# board.net
KiCad netlist of a schematic drawn in EAGLE
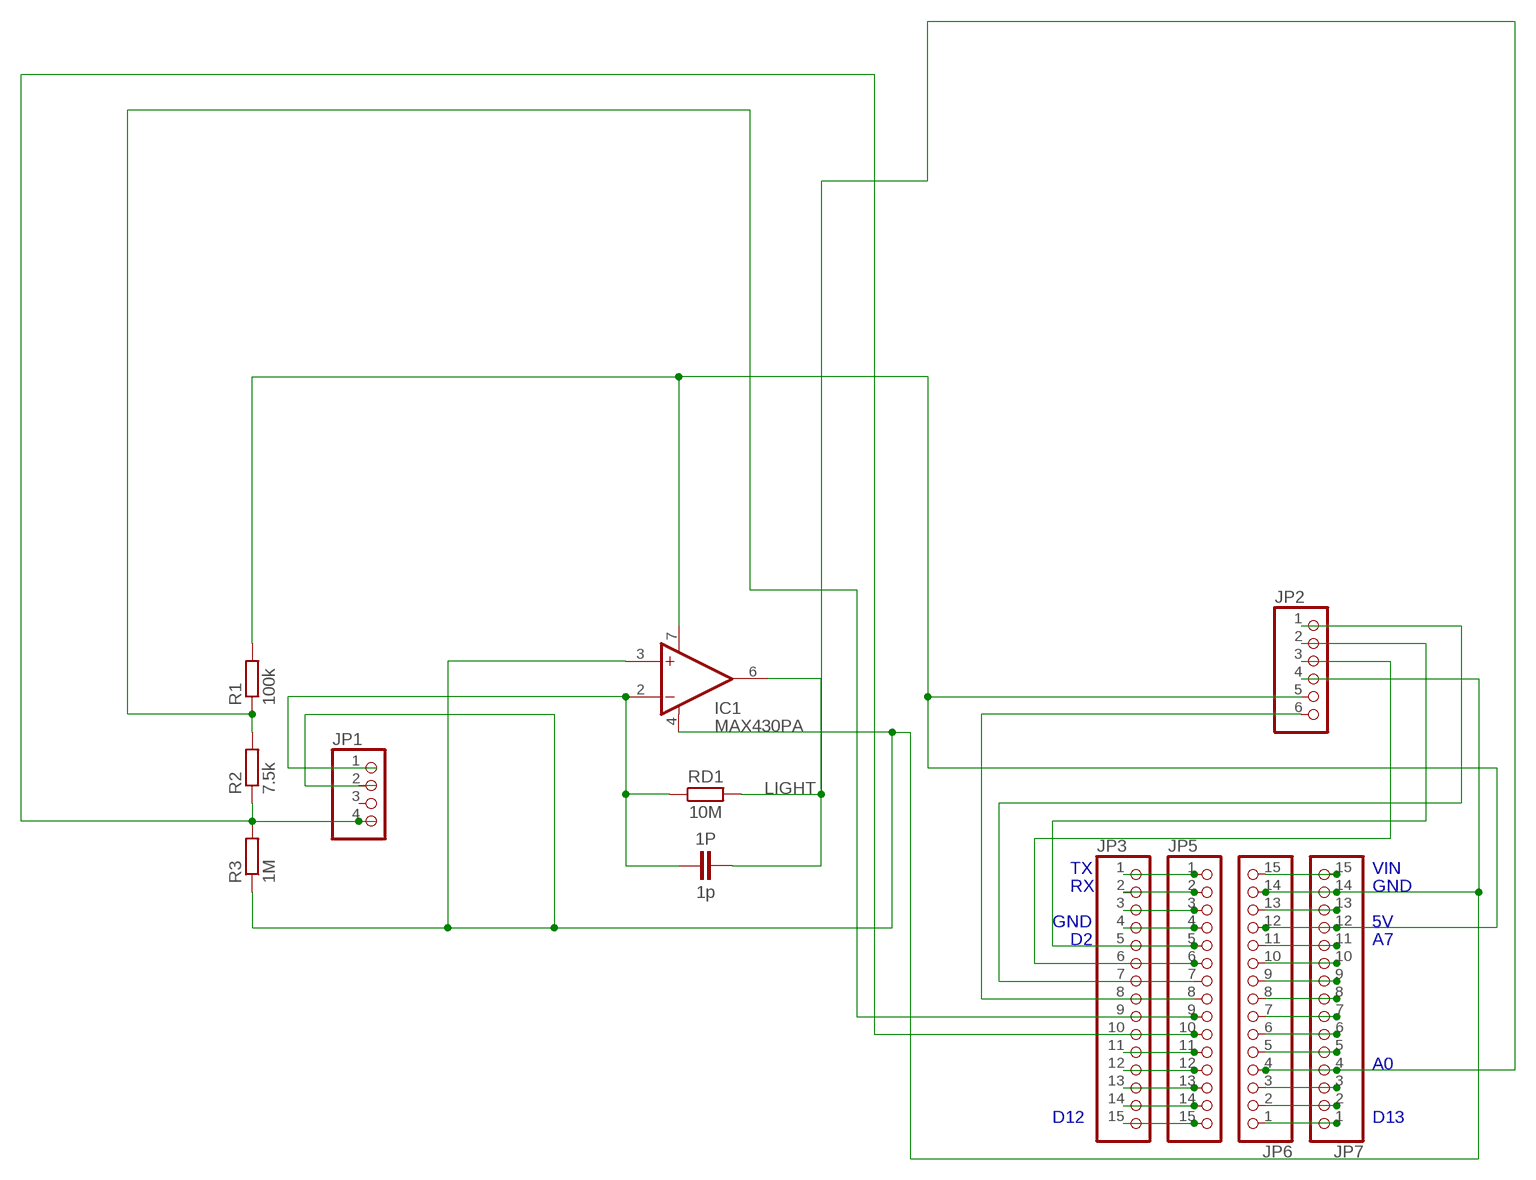
[diagram p0: schematic, sheet 1]

(export (version "E")
  (design (tool "Eeschema 10.0.6"))
  (components
    (comp (ref "1P")
      (value "1p")
      (footprint "eagle-import:1206")
      (libsource (lib "eagle-import") (part "CAPACITOR1206"))
    )
    (comp (ref "IC1")
      (value "MAX430PA")
      (footprint "eagle-import:DIL08")
      (libsource (lib "eagle-import") (part "MAX430PA"))
    )
    (comp (ref "JP1")
      (value "PINHD-1X4")
      (footprint "eagle-import:1X04")
      (libsource (lib "eagle-import") (part "PINHD-1X4"))
    )
    (comp (ref "JP2")
      (value "PINHD-1X6")
      (footprint "eagle-import:1X06")
      (libsource (lib "eagle-import") (part "PINHD-1X6"))
    )
    (comp (ref "JP3")
      (value "PINHD-1X15")
      (footprint "eagle-import:1X15")
      (libsource (lib "eagle-import") (part "PINHD-1X15"))
    )
    (comp (ref "JP5")
      (value "PINHD-1X15")
      (footprint "eagle-import:1X15")
      (libsource (lib "eagle-import") (part "PINHD-1X15"))
    )
    (comp (ref "JP6")
      (value "PINHD-1X15")
      (footprint "eagle-import:1X15")
      (libsource (lib "eagle-import") (part "PINHD-1X15"))
    )
    (comp (ref "JP7")
      (value "PINHD-1X15")
      (footprint "eagle-import:1X15")
      (libsource (lib "eagle-import") (part "PINHD-1X15"))
    )
    (comp (ref "R1")
      (value "100k")
      (footprint "eagle-import:R1206")
      (libsource (lib "eagle-import") (part "R-EU_R1206"))
    )
    (comp (ref "R2")
      (value "7.5k")
      (footprint "eagle-import:R1206")
      (libsource (lib "eagle-import") (part "R-EU_R1206"))
    )
    (comp (ref "R3")
      (value "1M")
      (footprint "eagle-import:R1206")
      (libsource (lib "eagle-import") (part "R-EU_R1206"))
    )
    (comp (ref "RD1")
      (value "10M")
      (footprint "eagle-import:1206")
      (libsource (lib "eagle-import") (part "RESISTOR1206"))
    )
  )
  (nets
    (net (code "1") (name "/LIGHT") (class "Default")
      (node (ref "1P") (pin "2") (pinfunction "2_2") (pintype "passive"))
      (node (ref "IC1") (pin "6") (pinfunction "OUT_6") (pintype "output"))
      (node (ref "JP6") (pin "4") (pinfunction "4_4") (pintype "passive"))
      (node (ref "JP7") (pin "4") (pinfunction "4_4") (pintype "passive"))
      (node (ref "RD1") (pin "2") (pinfunction "2_2") (pintype "passive"))
    )
    (net (code "2") (name "Net-(IC1-+IN)") (class "Default")
      (node (ref "IC1") (pin "3") (pinfunction "+IN_3") (pintype "input"))
      (node (ref "IC1") (pin "4") (pinfunction "V-_4") (pintype "power_in"))
      (node (ref "JP1") (pin "2") (pinfunction "2_2") (pintype "passive"))
      (node (ref "JP2") (pin "4") (pinfunction "4_4") (pintype "passive"))
      (node (ref "JP6") (pin "14") (pinfunction "14_14") (pintype "passive"))
      (node (ref "JP7") (pin "14") (pinfunction "14_14") (pintype "passive"))
      (node (ref "R3") (pin "1") (pinfunction "1_1") (pintype "passive"))
    )
    (net (code "3") (name "Net-(IC1--IN)") (class "Default")
      (node (ref "1P") (pin "1") (pinfunction "1_1") (pintype "passive"))
      (node (ref "IC1") (pin "2") (pinfunction "-IN_2") (pintype "input"))
      (node (ref "JP1") (pin "1") (pinfunction "1_1") (pintype "passive"))
      (node (ref "RD1") (pin "1") (pinfunction "1_1") (pintype "passive"))
    )
    (net (code "4") (name "Net-(IC1-V+)") (class "Default")
      (node (ref "IC1") (pin "7") (pinfunction "V+_7") (pintype "power_in"))
      (node (ref "JP2") (pin "5") (pinfunction "5_5") (pintype "passive"))
      (node (ref "JP6") (pin "12") (pinfunction "12_12") (pintype "passive"))
      (node (ref "JP7") (pin "12") (pinfunction "12_12") (pintype "passive"))
      (node (ref "R1") (pin "2") (pinfunction "2_2") (pintype "passive"))
    )
    (net (code "5") (name "Net-(JP1-Pad4)") (class "Default")
      (node (ref "JP1") (pin "4") (pinfunction "4_4") (pintype "passive"))
      (node (ref "JP3") (pin "10") (pinfunction "10_10") (pintype "passive"))
      (node (ref "JP5") (pin "10") (pinfunction "10_10") (pintype "passive"))
      (node (ref "R2") (pin "1") (pinfunction "1_1") (pintype "passive"))
      (node (ref "R3") (pin "2") (pinfunction "2_2") (pintype "passive"))
    )
    (net (code "6") (name "Net-(JP2-Pad1)") (class "Default")
      (node (ref "JP2") (pin "1") (pinfunction "1_1") (pintype "passive"))
      (node (ref "JP3") (pin "7") (pinfunction "7_7") (pintype "passive"))
      (node (ref "JP5") (pin "7") (pinfunction "7_7") (pintype "passive"))
    )
    (net (code "7") (name "Net-(JP2-Pad2)") (class "Default")
      (node (ref "JP2") (pin "2") (pinfunction "2_2") (pintype "passive"))
      (node (ref "JP3") (pin "5") (pinfunction "5_5") (pintype "passive"))
      (node (ref "JP5") (pin "5") (pinfunction "5_5") (pintype "passive"))
    )
    (net (code "8") (name "Net-(JP2-Pad3)") (class "Default")
      (node (ref "JP2") (pin "3") (pinfunction "3_3") (pintype "passive"))
      (node (ref "JP3") (pin "6") (pinfunction "6_6") (pintype "passive"))
      (node (ref "JP5") (pin "6") (pinfunction "6_6") (pintype "passive"))
    )
    (net (code "9") (name "Net-(JP2-Pad6)") (class "Default")
      (node (ref "JP2") (pin "6") (pinfunction "6_6") (pintype "passive"))
      (node (ref "JP3") (pin "8") (pinfunction "8_8") (pintype "passive"))
      (node (ref "JP5") (pin "8") (pinfunction "8_8") (pintype "passive"))
    )
    (net (code "10") (name "Net-(JP3-Pad1)") (class "Default")
      (node (ref "JP3") (pin "1") (pinfunction "1_1") (pintype "passive"))
      (node (ref "JP5") (pin "1") (pinfunction "1_1") (pintype "passive"))
    )
    (net (code "11") (name "Net-(JP3-Pad2)") (class "Default")
      (node (ref "JP3") (pin "2") (pinfunction "2_2") (pintype "passive"))
      (node (ref "JP5") (pin "2") (pinfunction "2_2") (pintype "passive"))
    )
    (net (code "12") (name "Net-(JP3-Pad3)") (class "Default")
      (node (ref "JP3") (pin "3") (pinfunction "3_3") (pintype "passive"))
      (node (ref "JP5") (pin "3") (pinfunction "3_3") (pintype "passive"))
    )
    (net (code "13") (name "Net-(JP3-Pad4)") (class "Default")
      (node (ref "JP3") (pin "4") (pinfunction "4_4") (pintype "passive"))
      (node (ref "JP5") (pin "4") (pinfunction "4_4") (pintype "passive"))
    )
    (net (code "14") (name "Net-(JP3-Pad9)") (class "Default")
      (node (ref "JP3") (pin "9") (pinfunction "9_9") (pintype "passive"))
      (node (ref "JP5") (pin "9") (pinfunction "9_9") (pintype "passive"))
      (node (ref "R1") (pin "1") (pinfunction "1_1") (pintype "passive"))
      (node (ref "R2") (pin "2") (pinfunction "2_2") (pintype "passive"))
    )
    (net (code "15") (name "Net-(JP3-Pad11)") (class "Default")
      (node (ref "JP3") (pin "11") (pinfunction "11_11") (pintype "passive"))
      (node (ref "JP5") (pin "11") (pinfunction "11_11") (pintype "passive"))
    )
    (net (code "16") (name "Net-(JP3-Pad12)") (class "Default")
      (node (ref "JP3") (pin "12") (pinfunction "12_12") (pintype "passive"))
      (node (ref "JP5") (pin "12") (pinfunction "12_12") (pintype "passive"))
    )
    (net (code "17") (name "Net-(JP3-Pad13)") (class "Default")
      (node (ref "JP3") (pin "13") (pinfunction "13_13") (pintype "passive"))
      (node (ref "JP5") (pin "13") (pinfunction "13_13") (pintype "passive"))
    )
    (net (code "18") (name "Net-(JP3-Pad14)") (class "Default")
      (node (ref "JP3") (pin "14") (pinfunction "14_14") (pintype "passive"))
      (node (ref "JP5") (pin "14") (pinfunction "14_14") (pintype "passive"))
    )
    (net (code "19") (name "Net-(JP3-Pad15)") (class "Default")
      (node (ref "JP3") (pin "15") (pinfunction "15_15") (pintype "passive"))
      (node (ref "JP5") (pin "15") (pinfunction "15_15") (pintype "passive"))
    )
    (net (code "20") (name "Net-(JP6-Pad1)") (class "Default")
      (node (ref "JP6") (pin "1") (pinfunction "1_1") (pintype "passive"))
      (node (ref "JP7") (pin "1") (pinfunction "1_1") (pintype "passive"))
    )
    (net (code "21") (name "Net-(JP6-Pad2)") (class "Default")
      (node (ref "JP6") (pin "2") (pinfunction "2_2") (pintype "passive"))
      (node (ref "JP7") (pin "2") (pinfunction "2_2") (pintype "passive"))
    )
    (net (code "22") (name "Net-(JP6-Pad3)") (class "Default")
      (node (ref "JP6") (pin "3") (pinfunction "3_3") (pintype "passive"))
      (node (ref "JP7") (pin "3") (pinfunction "3_3") (pintype "passive"))
    )
    (net (code "23") (name "Net-(JP6-Pad5)") (class "Default")
      (node (ref "JP6") (pin "5") (pinfunction "5_5") (pintype "passive"))
      (node (ref "JP7") (pin "5") (pinfunction "5_5") (pintype "passive"))
    )
    (net (code "24") (name "Net-(JP6-Pad6)") (class "Default")
      (node (ref "JP6") (pin "6") (pinfunction "6_6") (pintype "passive"))
      (node (ref "JP7") (pin "6") (pinfunction "6_6") (pintype "passive"))
    )
    (net (code "25") (name "Net-(JP6-Pad7)") (class "Default")
      (node (ref "JP6") (pin "7") (pinfunction "7_7") (pintype "passive"))
      (node (ref "JP7") (pin "7") (pinfunction "7_7") (pintype "passive"))
    )
    (net (code "26") (name "Net-(JP6-Pad8)") (class "Default")
      (node (ref "JP6") (pin "8") (pinfunction "8_8") (pintype "passive"))
      (node (ref "JP7") (pin "8") (pinfunction "8_8") (pintype "passive"))
    )
    (net (code "27") (name "Net-(JP6-Pad9)") (class "Default")
      (node (ref "JP6") (pin "9") (pinfunction "9_9") (pintype "passive"))
      (node (ref "JP7") (pin "9") (pinfunction "9_9") (pintype "passive"))
    )
    (net (code "28") (name "Net-(JP6-Pad10)") (class "Default")
      (node (ref "JP6") (pin "10") (pinfunction "10_10") (pintype "passive"))
      (node (ref "JP7") (pin "10") (pinfunction "10_10") (pintype "passive"))
    )
    (net (code "29") (name "Net-(JP6-Pad11)") (class "Default")
      (node (ref "JP6") (pin "11") (pinfunction "11_11") (pintype "passive"))
      (node (ref "JP7") (pin "11") (pinfunction "11_11") (pintype "passive"))
    )
    (net (code "30") (name "Net-(JP6-Pad13)") (class "Default")
      (node (ref "JP6") (pin "13") (pinfunction "13_13") (pintype "passive"))
      (node (ref "JP7") (pin "13") (pinfunction "13_13") (pintype "passive"))
    )
    (net (code "31") (name "Net-(JP6-Pad15)") (class "Default")
      (node (ref "JP6") (pin "15") (pinfunction "15_15") (pintype "passive"))
      (node (ref "JP7") (pin "15") (pinfunction "15_15") (pintype "passive"))
    )
    (net (code "32") (name "unconnected-(JP1-Pad3)") (class "Default")
      (node (ref "JP1") (pin "3") (pinfunction "3_3") (pintype "passive"))
    )
  )
)
